# P_iron_V3_0_2020-11-07_00-05-42.net
KiCad netlist of a schematic drawn in Altium Designer
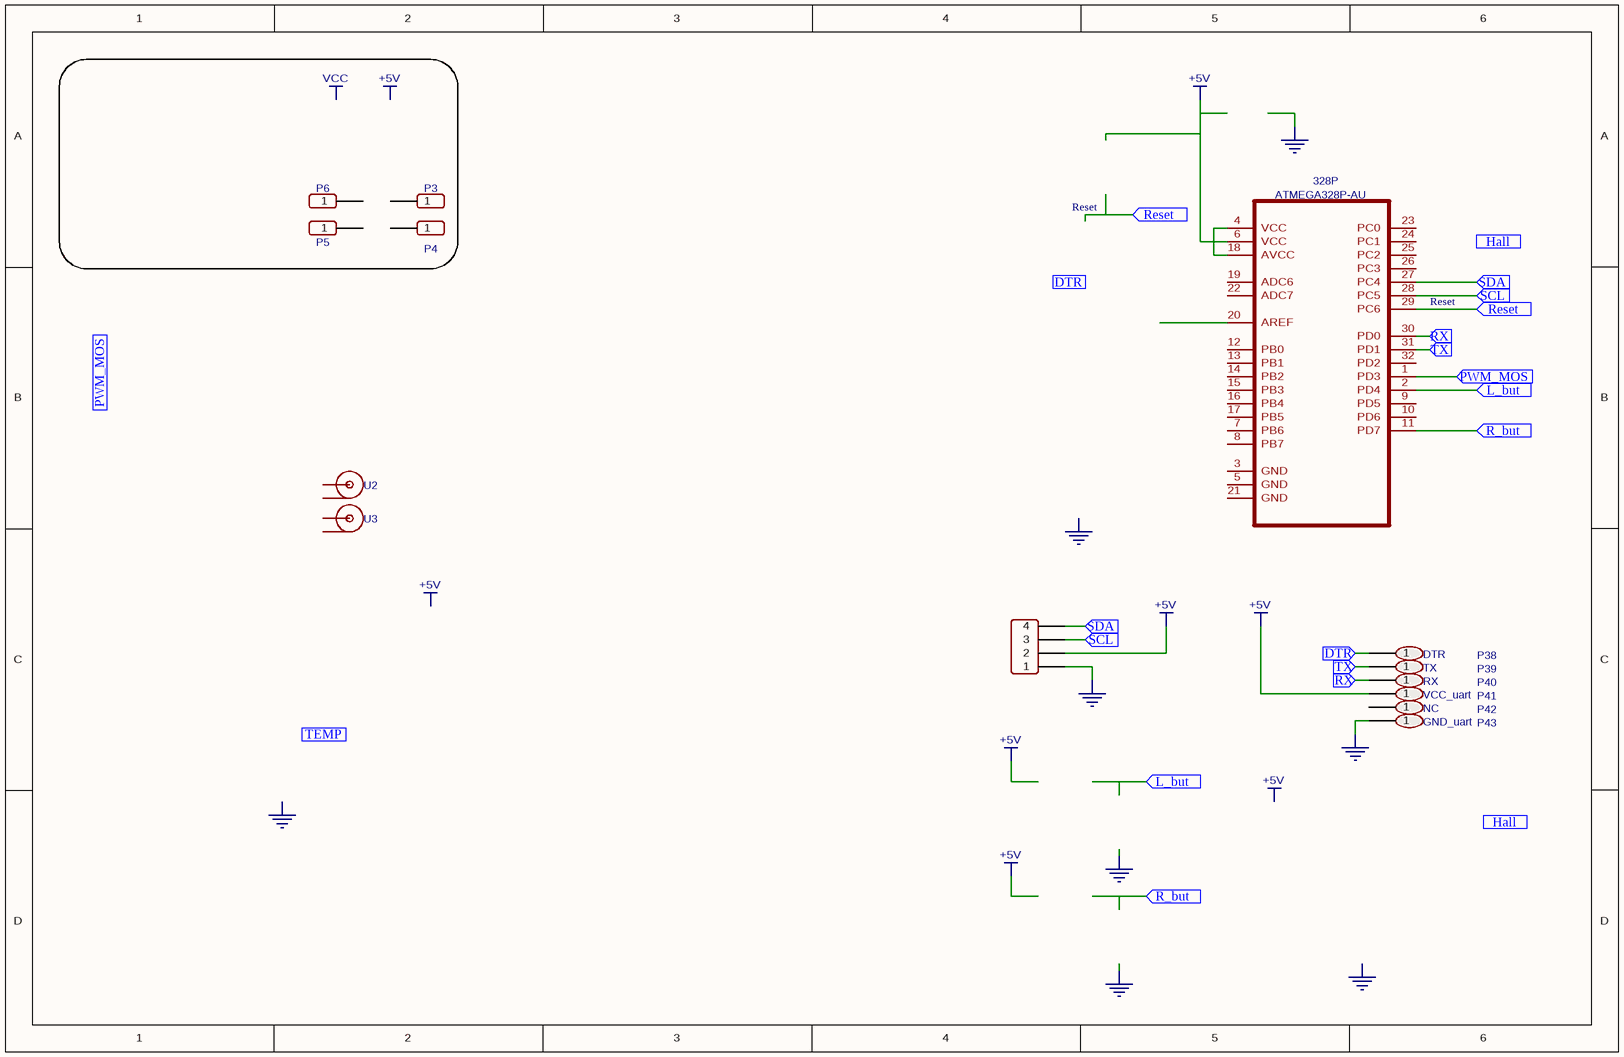
[diagram p0: P_iron_V3.0_2020-11-07_00-05-42.schdoc]

(export (version "E")
  (design (tool "Eeschema 10.0.6"))
  (components
    (comp (ref "328P")
      (value "ATMEGA328P-AU")
      (fields (field (name "BOM_MANUFACTURER PART") "?"))
      (libsource (lib "altium-import") (part "root_0_ATMEGA328P-AU_"))
    )
    (comp (ref "P1")
      (value "i2c_OLED")
      (fields
        (field (name "BOM_MANUFACTURER PART") "Headers  Pins 1*4P")
        (field (name "BOM_SUPPLIER PART") "undefined")
      )
      (libsource (lib "altium-import") (part "root_2_i2c_OLED_"))
    )
    (comp (ref "P3")
      (value "Header 1*1P")
      (fields (field (name "BOM_SUPPLIER PART") "C81276"))
      (libsource (lib "altium-import") (part "root_0_Header 1*1P_"))
    )
    (comp (ref "P4")
      (value "Header 1*1P")
      (fields (field (name "BOM_SUPPLIER PART") "C81276"))
      (libsource (lib "altium-import") (part "root_0_Header 1*1P_"))
    )
    (comp (ref "P5")
      (value "Header 1*1P")
      (fields (field (name "BOM_SUPPLIER PART") "C81276"))
      (libsource (lib "altium-import") (part "root_2_Header 1*1P_"))
    )
    (comp (ref "P6")
      (value "Header 1*1P")
      (fields (field (name "BOM_SUPPLIER PART") "C81276"))
      (libsource (lib "altium-import") (part "root_2_Header 1*1P_"))
    )
    (comp (ref "P38")
      (value "DTR")
      (fields
        (field (name "BOM_MANUFACTURER PART") "Header 1*1P")
        (field (name "BOM_SUPPLIER PART") "C81276")
      )
      (libsource (lib "altium-import") (part "root_0_DTR_"))
    )
    (comp (ref "P39")
      (value "TX")
      (fields
        (field (name "BOM_MANUFACTURER PART") "Header 1*1P")
        (field (name "BOM_SUPPLIER PART") "C81276")
      )
      (libsource (lib "altium-import") (part "root_0_TX_"))
    )
    (comp (ref "P40")
      (value "RX")
      (fields
        (field (name "BOM_MANUFACTURER PART") "Header 1*1P")
        (field (name "BOM_SUPPLIER PART") "C81276")
      )
      (libsource (lib "altium-import") (part "root_0_RX_"))
    )
    (comp (ref "P41")
      (value "VCC_uart")
      (fields
        (field (name "BOM_MANUFACTURER PART") "Header 1*1P")
        (field (name "BOM_SUPPLIER PART") "C81276")
      )
      (libsource (lib "altium-import") (part "root_0_VCC_uart_"))
    )
    (comp (ref "P42")
      (value "NC")
      (fields
        (field (name "BOM_MANUFACTURER PART") "Header 1*1P")
        (field (name "BOM_SUPPLIER PART") "C81276")
      )
      (libsource (lib "altium-import") (part "root_0_NC_"))
    )
    (comp (ref "P43")
      (value "GND_uart")
      (fields
        (field (name "BOM_MANUFACTURER PART") "Header 1*1P")
        (field (name "BOM_SUPPLIER PART") "C81276")
      )
      (libsource (lib "altium-import") (part "root_0_GND_uart_"))
    )
    (comp (ref "U2")
      (value "Fuse clip 1p TH")
      (fields
        (field (name "BOM_MANUFACTURER PART") "5x20 RHOS Fuse clip/seat")
        (field (name "BOM_SUPPLIER PART") "C3130")
        (field (name "CONTRIBUTOR") "gjt211")
      )
      (libsource (lib "altium-import") (part "root_0_Fuse clip 1p TH_"))
    )
    (comp (ref "U3")
      (value "Fuse clip 1p TH")
      (fields
        (field (name "BOM_MANUFACTURER PART") "5x20 RHOS Fuse clip/seat")
        (field (name "BOM_SUPPLIER PART") "C3130")
        (field (name "CONTRIBUTOR") "gjt211")
      )
      (libsource (lib "altium-import") (part "root_0_Fuse clip 1p TH_"))
    )
  )
  (nets
    (net (code "1") (name "+5V") (class "Default")
      (node (ref "328P") (pin "18") (pinfunction "AVCC_18") (pintype "passive"))
      (node (ref "328P") (pin "4") (pinfunction "VCC_4") (pintype "passive"))
      (node (ref "328P") (pin "6") (pinfunction "VCC_6") (pintype "passive"))
      (node (ref "P1") (pin "2") (pinfunction "2_2") (pintype "passive"))
      (node (ref "P41") (pin "1") (pinfunction "1_1") (pintype "passive"))
    )
    (net (code "2") (name "/DTR") (class "Default")
      (node (ref "P38") (pin "1") (pinfunction "1_1") (pintype "passive"))
    )
    (net (code "4") (name "/L_but") (class "Default")
      (node (ref "328P") (pin "2") (pinfunction "PD4_2") (pintype "passive"))
    )
    (net (code "5") (name "/PWM_MOS") (class "Default")
      (node (ref "328P") (pin "1") (pinfunction "PD3_1") (pintype "passive"))
    )
    (net (code "6") (name "/RX") (class "Default")
      (node (ref "328P") (pin "30") (pinfunction "PD0_30") (pintype "passive"))
      (node (ref "P40") (pin "1") (pinfunction "1_1") (pintype "passive"))
    )
    (net (code "7") (name "/R_but") (class "Default")
      (node (ref "328P") (pin "11") (pinfunction "PD7_11") (pintype "passive"))
    )
    (net (code "8") (name "/Reset") (class "Default")
      (node (ref "328P") (pin "29") (pinfunction "PC6_29") (pintype "passive"))
    )
    (net (code "9") (name "/SCL") (class "Default")
      (node (ref "328P") (pin "28") (pinfunction "PC5_28") (pintype "passive"))
      (node (ref "P1") (pin "3") (pinfunction "3_3") (pintype "passive"))
    )
    (net (code "10") (name "/SDA") (class "Default")
      (node (ref "328P") (pin "27") (pinfunction "PC4_27") (pintype "passive"))
      (node (ref "P1") (pin "4") (pinfunction "4_4") (pintype "passive"))
    )
    (net (code "12") (name "/TX") (class "Default")
      (node (ref "328P") (pin "31") (pinfunction "PD1_31") (pintype "passive"))
      (node (ref "P39") (pin "1") (pinfunction "1_1") (pintype "passive"))
    )
    (net (code "13") (name "GND") (class "Default")
      (node (ref "P1") (pin "1") (pinfunction "1_1") (pintype "passive"))
      (node (ref "P43") (pin "1") (pinfunction "1_1") (pintype "passive"))
    )
    (net (code "15") (name "unconnected-(328P-ADC6-Pad19)") (class "Default")
      (node (ref "328P") (pin "19") (pinfunction "ADC6_19") (pintype "passive"))
    )
    (net (code "16") (name "unconnected-(328P-ADC7-Pad22)") (class "Default")
      (node (ref "328P") (pin "22") (pinfunction "ADC7_22") (pintype "passive"))
    )
    (net (code "17") (name "unconnected-(328P-AREF-Pad20)") (class "Default")
      (node (ref "328P") (pin "20") (pinfunction "AREF_20") (pintype "passive"))
    )
    (net (code "18") (name "unconnected-(328P-GND-Pad3)") (class "Default")
      (node (ref "328P") (pin "3") (pinfunction "GND_3") (pintype "passive"))
    )
    (net (code "19") (name "unconnected-(328P-GND-Pad5)") (class "Default")
      (node (ref "328P") (pin "5") (pinfunction "GND_5") (pintype "passive"))
    )
    (net (code "20") (name "unconnected-(328P-GND-Pad21)") (class "Default")
      (node (ref "328P") (pin "21") (pinfunction "GND_21") (pintype "passive"))
    )
    (net (code "21") (name "unconnected-(328P-PB0-Pad12)") (class "Default")
      (node (ref "328P") (pin "12") (pinfunction "PB0_12") (pintype "passive"))
    )
    (net (code "22") (name "unconnected-(328P-PB1-Pad13)") (class "Default")
      (node (ref "328P") (pin "13") (pinfunction "PB1_13") (pintype "passive"))
    )
    (net (code "23") (name "unconnected-(328P-PB2-Pad14)") (class "Default")
      (node (ref "328P") (pin "14") (pinfunction "PB2_14") (pintype "passive"))
    )
    (net (code "24") (name "unconnected-(328P-PB3-Pad15)") (class "Default")
      (node (ref "328P") (pin "15") (pinfunction "PB3_15") (pintype "passive"))
    )
    (net (code "25") (name "unconnected-(328P-PB4-Pad16)") (class "Default")
      (node (ref "328P") (pin "16") (pinfunction "PB4_16") (pintype "passive"))
    )
    (net (code "26") (name "unconnected-(328P-PB5-Pad17)") (class "Default")
      (node (ref "328P") (pin "17") (pinfunction "PB5_17") (pintype "passive"))
    )
    (net (code "27") (name "unconnected-(328P-PB6-Pad7)") (class "Default")
      (node (ref "328P") (pin "7") (pinfunction "PB6_7") (pintype "passive"))
    )
    (net (code "28") (name "unconnected-(328P-PB7-Pad8)") (class "Default")
      (node (ref "328P") (pin "8") (pinfunction "PB7_8") (pintype "passive"))
    )
    (net (code "29") (name "unconnected-(328P-PC0-Pad23)") (class "Default")
      (node (ref "328P") (pin "23") (pinfunction "PC0_23") (pintype "passive"))
    )
    (net (code "30") (name "unconnected-(328P-PC1-Pad24)") (class "Default")
      (node (ref "328P") (pin "24") (pinfunction "PC1_24") (pintype "passive"))
    )
    (net (code "31") (name "unconnected-(328P-PC2-Pad25)") (class "Default")
      (node (ref "328P") (pin "25") (pinfunction "PC2_25") (pintype "passive"))
    )
    (net (code "32") (name "unconnected-(328P-PC3-Pad26)") (class "Default")
      (node (ref "328P") (pin "26") (pinfunction "PC3_26") (pintype "passive"))
    )
    (net (code "33") (name "unconnected-(328P-PD2-Pad32)") (class "Default")
      (node (ref "328P") (pin "32") (pinfunction "PD2_32") (pintype "passive"))
    )
    (net (code "34") (name "unconnected-(328P-PD5-Pad9)") (class "Default")
      (node (ref "328P") (pin "9") (pinfunction "PD5_9") (pintype "passive"))
    )
    (net (code "35") (name "unconnected-(328P-PD6-Pad10)") (class "Default")
      (node (ref "328P") (pin "10") (pinfunction "PD6_10") (pintype "passive"))
    )
    (net (code "36") (name "unconnected-(P3-Pad1)") (class "Default")
      (node (ref "P3") (pin "1") (pinfunction "1_1") (pintype "passive"))
    )
    (net (code "37") (name "unconnected-(P4-Pad1)") (class "Default")
      (node (ref "P4") (pin "1") (pinfunction "1_1") (pintype "passive"))
    )
    (net (code "38") (name "unconnected-(P5-Pad1)") (class "Default")
      (node (ref "P5") (pin "1") (pinfunction "1_1") (pintype "passive"))
    )
    (net (code "39") (name "unconnected-(P6-Pad1)") (class "Default")
      (node (ref "P6") (pin "1") (pinfunction "1_1") (pintype "passive"))
    )
    (net (code "40") (name "unconnected-(P42-Pad1)") (class "Default")
      (node (ref "P42") (pin "1") (pinfunction "1_1") (pintype "passive"))
    )
    (net (code "41") (name "unconnected-(U2-Pad1)") (class "Default")
      (node (ref "U2") (pin "1") (pinfunction "1_1") (pintype "passive"))
    )
    (net (code "42") (name "unconnected-(U2-Pad1)_1") (class "Default")
      (node (ref "U2") (pin "1") (pinfunction "1_1") (pintype "passive"))
    )
    (net (code "43") (name "unconnected-(U3-Pad1)") (class "Default")
      (node (ref "U3") (pin "1") (pinfunction "1_1") (pintype "passive"))
    )
    (net (code "44") (name "unconnected-(U3-Pad1)_1") (class "Default")
      (node (ref "U3") (pin "1") (pinfunction "1_1") (pintype "passive"))
    )
  )
)
